# R2CD_Snubber_circuit.net
KiCad netlist of a schematic drawn in Altium Designer
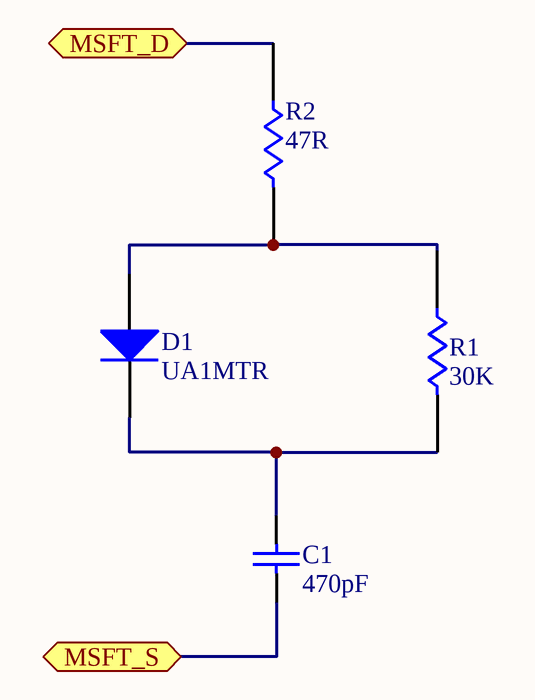
[diagram p0: R2CD Snubber circuit.SchDoc]

(export (version "E")
  (design (tool "Eeschema 10.0.6"))
  (components
    (comp (ref "C1")
      (value "C2220_Generic")
      (footprint "CAP2220")
      (fields (field (name "CAPACITANCE") "470pF"))
      (libsource (lib "ucc28180-V04") (part "C2220_Generic"))
    )
    (comp (ref "D1")
      (value "UA1MTR")
      (footprint "DO-214AC")
      (description "DIODE SCHOTTKY 1KV 1A SMA")
      (fields
        (field (name "MANUFACTURER") "SMC Diode Solutions")
        (field (name "MANUFACTURER PART NUMBER") "UA1MTR")
      )
      (libsource (lib "ucc28180-V04") (part "UA1MTR"))
    )
    (comp (ref "R1")
      (value "R2512_Generic")
      (footprint "RES2512")
      (fields (field (name "RESISTANCE") "30K"))
      (libsource (lib "ucc28180-V04") (part "R2512_Generic"))
    )
    (comp (ref "R2")
      (value "RMCF0805JT47R0")
      (footprint "RES0805_New")
      (description "RES SMD 47 OHM 5% 1/8W 0805")
      (fields
        (field (name "MANUFACTURER") "Stackpole Electronics Inc.")
        (field (name "TOLERANCE") "±5%")
        (field (name "RESISTANCE") "47R")
      )
      (libsource (lib "ucc28180-V04") (part "RMCF0805JT47R0"))
    )
  )
  (nets
    (net (code "1") (name "/MSFT_D") (class "Default")
      (node (ref "R2") (pin "1") (pinfunction "1_1") (pintype "passive"))
    )
    (net (code "2") (name "/MSFT_S") (class "Default")
      (node (ref "C1") (pin "1") (pinfunction "1_1") (pintype "passive"))
    )
    (net (code "3") (name "Net-(D1-A)") (class "Default")
      (node (ref "D1") (pin "2") (pinfunction "A_2") (pintype "passive"))
      (node (ref "R1") (pin "1") (pinfunction "1_1") (pintype "passive"))
      (node (ref "R2") (pin "2") (pinfunction "2_2") (pintype "passive"))
    )
    (net (code "4") (name "Net-(D1-K)") (class "Default")
      (node (ref "C1") (pin "2") (pinfunction "2_2") (pintype "passive"))
      (node (ref "D1") (pin "1") (pinfunction "K_1") (pintype "passive"))
      (node (ref "R1") (pin "2") (pinfunction "2_2") (pintype "passive"))
    )
  )
)
